# RoBeast_Driver.net
KiCad netlist of a schematic drawn in Altium Designer
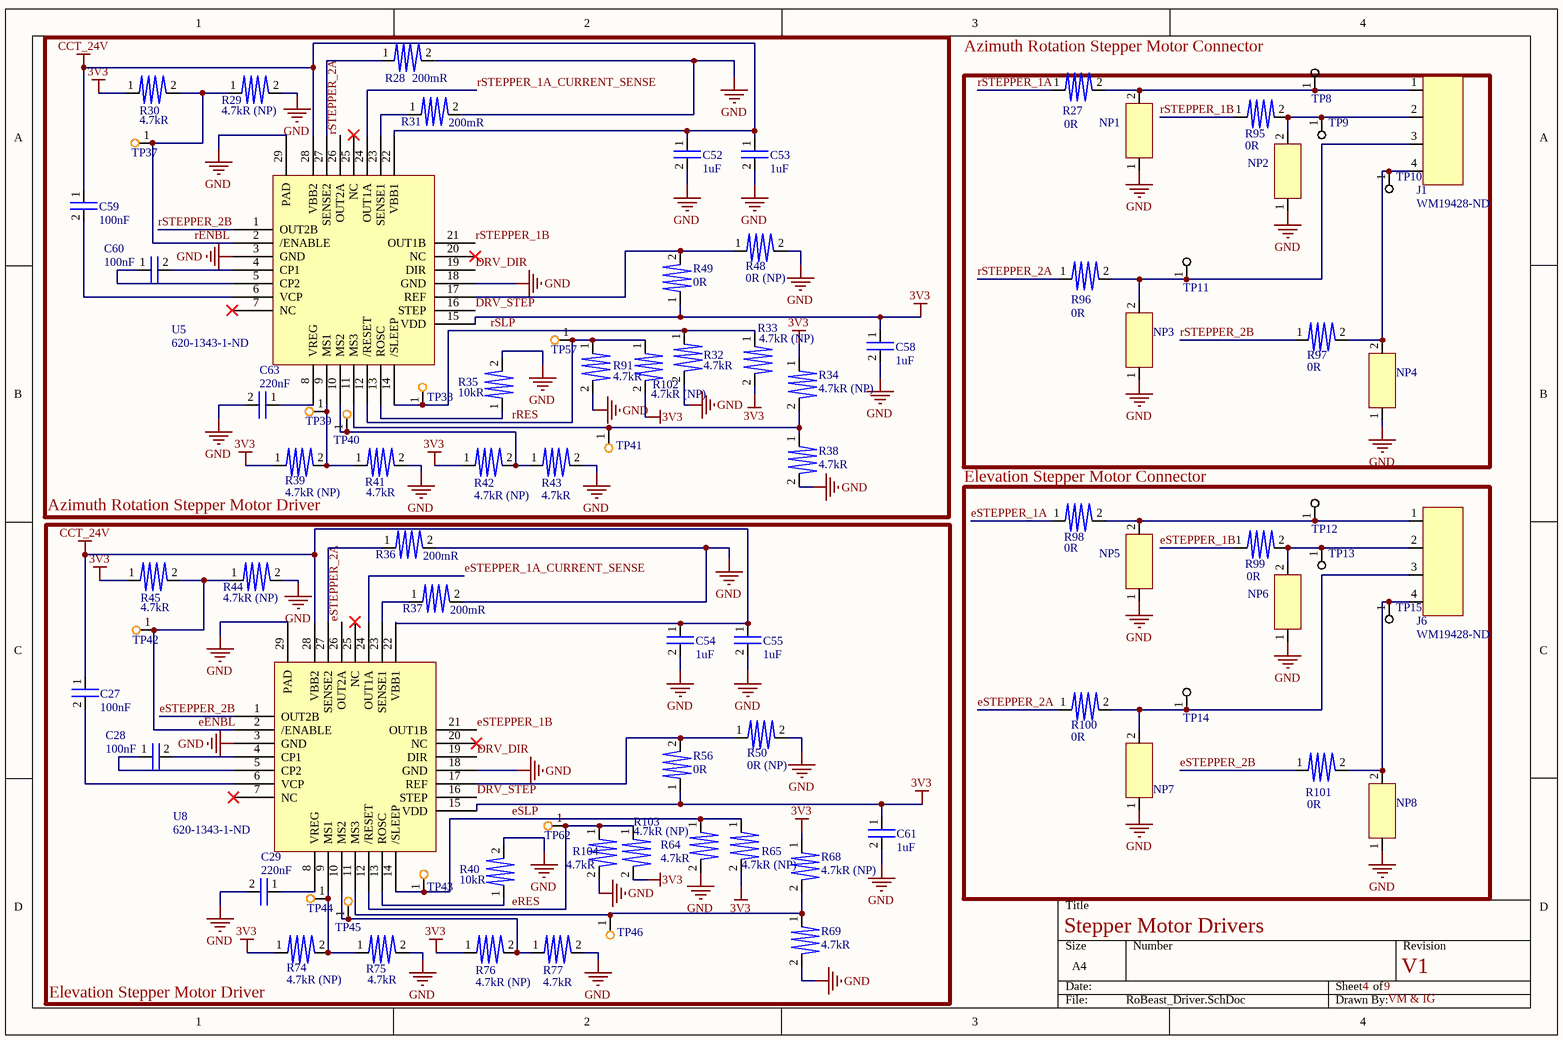
[diagram p0: RoBeast_Driver.SchDoc]

(export (version "E")
  (design (tool "Eeschema 10.0.6"))
  (components
    (comp (ref "C27")
      (value "100nF")
      (footprint "0805")
      (fields
        (field (name "MANUFACTURER") "KEMET")
        (field (name "MANUFACTURER PART NUMBER") "C0805C104J5RACTU")
      )
      (libsource (lib "RoBeast_Schematic_Library") (part "C0805C104J5RAC7800"))
    )
    (comp (ref "C28")
      (value "100nF")
      (footprint "0805")
      (fields
        (field (name "MANUFACTURER") "KEMET")
        (field (name "MANUFACTURER PART NUMBER") "C0805C104J5RACTU")
      )
      (libsource (lib "RoBeast_Schematic_Library") (part "C0805C104J5RAC7800"))
    )
    (comp (ref "C29")
      (value "220nF")
      (footprint "0805")
      (fields
        (field (name "MANUFACTURER") "KEMET")
        (field (name "MANUFACTURER PART NUMBER") "C0805C224J1RECAUTO")
      )
      (libsource (lib "RoBeast_Schematic_Library") (part "C0805C224J1RECAUTO"))
    )
    (comp (ref "C52")
      (value "1uF")
      (footprint "0805")
      (fields
        (field (name "MANUFACTURER") "Yageo")
        (field (name "MANUFACTURER PART NUMBER") "CC0805JKX7R9BB105")
      )
      (libsource (lib "RoBeast_Schematic_Library") (part "CC0805JKX7R9BB105"))
    )
    (comp (ref "C53")
      (value "1uF")
      (footprint "0805")
      (fields
        (field (name "MANUFACTURER") "Yageo")
        (field (name "MANUFACTURER PART NUMBER") "CC0805JKX7R9BB105")
      )
      (libsource (lib "RoBeast_Schematic_Library") (part "CC0805JKX7R9BB105"))
    )
    (comp (ref "C54")
      (value "1uF")
      (footprint "0805")
      (fields
        (field (name "MANUFACTURER") "Yageo")
        (field (name "MANUFACTURER PART NUMBER") "CC0805JKX7R9BB105")
      )
      (libsource (lib "RoBeast_Schematic_Library") (part "CC0805JKX7R9BB105"))
    )
    (comp (ref "C55")
      (value "1uF")
      (footprint "0805")
      (fields
        (field (name "MANUFACTURER") "Yageo")
        (field (name "MANUFACTURER PART NUMBER") "CC0805JKX7R9BB105")
      )
      (libsource (lib "RoBeast_Schematic_Library") (part "CC0805JKX7R9BB105"))
    )
    (comp (ref "C58")
      (value "1uF")
      (footprint "0805")
      (fields
        (field (name "MANUFACTURER") "Yageo")
        (field (name "MANUFACTURER PART NUMBER") "CC0805JKX7R9BB105")
      )
      (libsource (lib "RoBeast_Schematic_Library") (part "CC0805JKX7R9BB105"))
    )
    (comp (ref "C59")
      (value "100nF")
      (footprint "0805")
      (fields
        (field (name "MANUFACTURER") "KEMET")
        (field (name "MANUFACTURER PART NUMBER") "C0805C104J5RACTU")
      )
      (libsource (lib "RoBeast_Schematic_Library") (part "C0805C104J5RAC7800"))
    )
    (comp (ref "C60")
      (value "100nF")
      (footprint "0805")
      (fields
        (field (name "MANUFACTURER") "KEMET")
        (field (name "MANUFACTURER PART NUMBER") "C0805C104J5RACTU")
      )
      (libsource (lib "RoBeast_Schematic_Library") (part "C0805C104J5RAC7800"))
    )
    (comp (ref "C61")
      (value "1uF")
      (footprint "0805")
      (fields
        (field (name "MANUFACTURER") "Yageo")
        (field (name "MANUFACTURER PART NUMBER") "CC0805JKX7R9BB105")
      )
      (libsource (lib "RoBeast_Schematic_Library") (part "CC0805JKX7R9BB105"))
    )
    (comp (ref "C63")
      (value "220nF")
      (footprint "0805")
      (fields
        (field (name "MANUFACTURER") "KEMET")
        (field (name "MANUFACTURER PART NUMBER") "C0805C224J1RECAUTO")
      )
      (libsource (lib "RoBeast_Schematic_Library") (part "C0805C224J1RECAUTO"))
    )
    (comp (ref "J1")
      (value "4 Pin Connector")
      (footprint "0015246043")
      (description "Rectangular Power Connector, 4 Contact(s), Male, Solder Terminal, Receptacle")
      (fields
        (field (name "MANUFACTURER") "Molex")
        (field (name "MANUFACTURER PART NUMBER") "15-24-6043")
        (field (name "SUPPLIER PART NUMBER") "WM19428-ND")
      )
      (libsource (lib "RoBeast_Schematic_Library") (part "0015246043"))
    )
    (comp (ref "J6")
      (value "4 Pin Connector")
      (footprint "0015246043")
      (description "Rectangular Power Connector, 4 Contact(s), Male, Solder Terminal, Receptacle")
      (fields
        (field (name "MANUFACTURER") "Molex")
        (field (name "MANUFACTURER PART NUMBER") "15-24-6043")
        (field (name "SUPPLIER PART NUMBER") "WM19428-ND")
      )
      (libsource (lib "RoBeast_Schematic_Library") (part "0015246043"))
    )
    (comp (ref "NP1")
      (value "Not Populated")
      (footprint "0805")
      (libsource (lib "RoBeast_Schematic_Library") (part "NP"))
    )
    (comp (ref "NP2")
      (value "Not Populated")
      (footprint "0805")
      (libsource (lib "RoBeast_Schematic_Library") (part "NP"))
    )
    (comp (ref "NP3")
      (value "Not Populated")
      (footprint "0805")
      (libsource (lib "RoBeast_Schematic_Library") (part "NP"))
    )
    (comp (ref "NP4")
      (value "Not Populated")
      (footprint "0805")
      (libsource (lib "RoBeast_Schematic_Library") (part "NP"))
    )
    (comp (ref "NP5")
      (value "Not Populated")
      (footprint "0805")
      (libsource (lib "RoBeast_Schematic_Library") (part "NP"))
    )
    (comp (ref "NP6")
      (value "Not Populated")
      (footprint "0805")
      (libsource (lib "RoBeast_Schematic_Library") (part "NP"))
    )
    (comp (ref "NP7")
      (value "Not Populated")
      (footprint "0805")
      (libsource (lib "RoBeast_Schematic_Library") (part "NP"))
    )
    (comp (ref "NP8")
      (value "Not Populated")
      (footprint "0805")
      (libsource (lib "RoBeast_Schematic_Library") (part "NP"))
    )
    (comp (ref "R27")
      (value "0R")
      (footprint "0805")
      (description "Fixed Resistor, Metal Glaze/thick Film, 0.125W, 0ohm, Surface Mount, 0805")
      (fields
        (field (name "MANUFACTURER") "Stackpole Electronics")
        (field (name "MANUFACTURER PART NUMBER") "RMCF0805ZT0R00")
      )
      (libsource (lib "RoBeast_Schematic_Library") (part "RMCF0805ZT0R00"))
    )
    (comp (ref "R28")
      (value "200mR")
      (footprint "0805")
      (description "Res 0805 50PPM 0.2 Ohm 1.0% 0.75")
      (fields
        (field (name "MANUFACTURER") "Thin Film Tech")
        (field (name "MANUFACTURER PART NUMBER") "D1WEL0805CR200F-T5")
      )
      (libsource (lib "RoBeast_Schematic_Library") (part "D1WEL0805CR200F-T5"))
    )
    (comp (ref "R29")
      (value "4.7kR (NP)")
      (footprint "0805")
      (fields
        (field (name "MANUFACTURER") "Vishay Dale")
        (field (name "MANUFACTURER PART NUMBER") "RCC08054K70FKEA")
      )
      (libsource (lib "RoBeast_Schematic_Library") (part "RCC08054K70FKEA"))
    )
    (comp (ref "R30")
      (value "4.7kR")
      (footprint "0805")
      (fields
        (field (name "MANUFACTURER") "Vishay Dale")
        (field (name "MANUFACTURER PART NUMBER") "RCC08054K70FKEA")
      )
      (libsource (lib "RoBeast_Schematic_Library") (part "RCC08054K70FKEA"))
    )
    (comp (ref "R31")
      (value "200mR")
      (footprint "0805")
      (description "Res 0805 50PPM 0.2 Ohm 1.0% 0.75")
      (fields
        (field (name "MANUFACTURER") "Thin Film Tech")
        (field (name "MANUFACTURER PART NUMBER") "D1WEL0805CR200F-T5")
      )
      (libsource (lib "RoBeast_Schematic_Library") (part "D1WEL0805CR200F-T5"))
    )
    (comp (ref "R32")
      (value "4.7kR")
      (footprint "0805")
      (fields
        (field (name "MANUFACTURER") "Vishay Dale")
        (field (name "MANUFACTURER PART NUMBER") "RCC08054K70FKEA")
      )
      (libsource (lib "RoBeast_Schematic_Library") (part "RCC08054K70FKEA"))
    )
    (comp (ref "R33")
      (value "4.7kR (NP)")
      (footprint "0805")
      (fields
        (field (name "MANUFACTURER") "Vishay Dale")
        (field (name "MANUFACTURER PART NUMBER") "RCC08054K70FKEA")
      )
      (libsource (lib "RoBeast_Schematic_Library") (part "RCC08054K70FKEA"))
    )
    (comp (ref "R34")
      (value "4.7kR (NP)")
      (footprint "0805")
      (fields
        (field (name "MANUFACTURER") "Vishay Dale")
        (field (name "MANUFACTURER PART NUMBER") "RCC08054K70FKEA")
      )
      (libsource (lib "RoBeast_Schematic_Library") (part "RCC08054K70FKEA"))
    )
    (comp (ref "R35")
      (value "10kR")
      (footprint "0805")
      (fields
        (field (name "MANUFACTURER") "Stackpole Electronics")
        (field (name "MANUFACTURER PART NUMBER") "RMCF0805FT10K0")
        (field (name "TOLERANCE") "1%")
      )
      (libsource (lib "RoBeast_Schematic_Library") (part "RMCF0805FT10K0"))
    )
    (comp (ref "R36")
      (value "200mR")
      (footprint "0805")
      (description "Res 0805 50PPM 0.2 Ohm 1.0% 0.75")
      (fields
        (field (name "MANUFACTURER") "Thin Film Tech")
        (field (name "MANUFACTURER PART NUMBER") "D1WEL0805CR200F-T5")
      )
      (libsource (lib "RoBeast_Schematic_Library") (part "D1WEL0805CR200F-T5"))
    )
    (comp (ref "R37")
      (value "200mR")
      (footprint "0805")
      (description "Res 0805 50PPM 0.2 Ohm 1.0% 0.75")
      (fields
        (field (name "MANUFACTURER") "Thin Film Tech")
        (field (name "MANUFACTURER PART NUMBER") "D1WEL0805CR200F-T5")
      )
      (libsource (lib "RoBeast_Schematic_Library") (part "D1WEL0805CR200F-T5"))
    )
    (comp (ref "R38")
      (value "4.7kR")
      (footprint "0805")
      (fields
        (field (name "MANUFACTURER") "Vishay Dale")
        (field (name "MANUFACTURER PART NUMBER") "RCC08054K70FKEA")
      )
      (libsource (lib "RoBeast_Schematic_Library") (part "RCC08054K70FKEA"))
    )
    (comp (ref "R39")
      (value "4.7kR (NP)")
      (footprint "0805")
      (fields
        (field (name "MANUFACTURER") "Vishay Dale")
        (field (name "MANUFACTURER PART NUMBER") "RCC08054K70FKEA")
      )
      (libsource (lib "RoBeast_Schematic_Library") (part "RCC08054K70FKEA"))
    )
    (comp (ref "R40")
      (value "10kR")
      (footprint "0805")
      (fields
        (field (name "MANUFACTURER") "Stackpole Electronics")
        (field (name "MANUFACTURER PART NUMBER") "RMCF0805FT10K0")
        (field (name "TOLERANCE") "1%")
      )
      (libsource (lib "RoBeast_Schematic_Library") (part "RMCF0805FT10K0"))
    )
    (comp (ref "R41")
      (value "4.7kR")
      (footprint "0805")
      (fields
        (field (name "MANUFACTURER") "Vishay Dale")
        (field (name "MANUFACTURER PART NUMBER") "RCC08054K70FKEA")
      )
      (libsource (lib "RoBeast_Schematic_Library") (part "RCC08054K70FKEA"))
    )
    (comp (ref "R42")
      (value "4.7kR (NP)")
      (footprint "0805")
      (fields
        (field (name "MANUFACTURER") "Vishay Dale")
        (field (name "MANUFACTURER PART NUMBER") "RCC08054K70FKEA")
      )
      (libsource (lib "RoBeast_Schematic_Library") (part "RCC08054K70FKEA"))
    )
    (comp (ref "R43")
      (value "4.7kR")
      (footprint "0805")
      (fields
        (field (name "MANUFACTURER") "Vishay Dale")
        (field (name "MANUFACTURER PART NUMBER") "RCC08054K70FKEA")
      )
      (libsource (lib "RoBeast_Schematic_Library") (part "RCC08054K70FKEA"))
    )
    (comp (ref "R44")
      (value "4.7kR (NP)")
      (footprint "0805")
      (fields
        (field (name "MANUFACTURER") "Vishay Dale")
        (field (name "MANUFACTURER PART NUMBER") "RCC08054K70FKEA")
      )
      (libsource (lib "RoBeast_Schematic_Library") (part "RCC08054K70FKEA"))
    )
    (comp (ref "R45")
      (value "4.7kR")
      (footprint "0805")
      (fields
        (field (name "MANUFACTURER") "Vishay Dale")
        (field (name "MANUFACTURER PART NUMBER") "RCC08054K70FKEA")
      )
      (libsource (lib "RoBeast_Schematic_Library") (part "RCC08054K70FKEA"))
    )
    (comp (ref "R48")
      (value "0R (NP)")
      (footprint "0805")
      (description "Fixed Resistor, Metal Glaze/thick Film, 0.125W, 0ohm, Surface Mount, 0805")
      (fields
        (field (name "MANUFACTURER") "Stackpole Electronics")
        (field (name "MANUFACTURER PART NUMBER") "RMCF0805ZT0R00")
      )
      (libsource (lib "RoBeast_Schematic_Library") (part "RMCF0805ZT0R00"))
    )
    (comp (ref "R49")
      (value "0R")
      (footprint "0805")
      (description "Fixed Resistor, Metal Glaze/thick Film, 0.125W, 0ohm, Surface Mount, 0805")
      (fields
        (field (name "MANUFACTURER") "Stackpole Electronics")
        (field (name "MANUFACTURER PART NUMBER") "RMCF0805ZT0R00")
      )
      (libsource (lib "RoBeast_Schematic_Library") (part "RMCF0805ZT0R00"))
    )
    (comp (ref "R50")
      (value "0R (NP)")
      (footprint "0805")
      (description "Fixed Resistor, Metal Glaze/thick Film, 0.125W, 0ohm, Surface Mount, 0805")
      (fields
        (field (name "MANUFACTURER") "Stackpole Electronics")
        (field (name "MANUFACTURER PART NUMBER") "RMCF0805ZT0R00")
      )
      (libsource (lib "RoBeast_Schematic_Library") (part "RMCF0805ZT0R00"))
    )
    (comp (ref "R56")
      (value "0R")
      (footprint "0805")
      (description "Fixed Resistor, Metal Glaze/thick Film, 0.125W, 0ohm, Surface Mount, 0805")
      (fields
        (field (name "MANUFACTURER") "Stackpole Electronics")
        (field (name "MANUFACTURER PART NUMBER") "RMCF0805ZT0R00")
      )
      (libsource (lib "RoBeast_Schematic_Library") (part "RMCF0805ZT0R00"))
    )
    (comp (ref "R64")
      (value "4.7kR")
      (footprint "0805")
      (fields
        (field (name "MANUFACTURER") "Vishay Dale")
        (field (name "MANUFACTURER PART NUMBER") "RCC08054K70FKEA")
      )
      (libsource (lib "RoBeast_Schematic_Library") (part "RCC08054K70FKEA"))
    )
    (comp (ref "R65")
      (value "4.7kR (NP)")
      (footprint "0805")
      (fields
        (field (name "MANUFACTURER") "Vishay Dale")
        (field (name "MANUFACTURER PART NUMBER") "RCC08054K70FKEA")
      )
      (libsource (lib "RoBeast_Schematic_Library") (part "RCC08054K70FKEA"))
    )
    (comp (ref "R68")
      (value "4.7kR (NP)")
      (footprint "0805")
      (fields
        (field (name "MANUFACTURER") "Vishay Dale")
        (field (name "MANUFACTURER PART NUMBER") "RCC08054K70FKEA")
      )
      (libsource (lib "RoBeast_Schematic_Library") (part "RCC08054K70FKEA"))
    )
    (comp (ref "R69")
      (value "4.7kR")
      (footprint "0805")
      (fields
        (field (name "MANUFACTURER") "Vishay Dale")
        (field (name "MANUFACTURER PART NUMBER") "RCC08054K70FKEA")
      )
      (libsource (lib "RoBeast_Schematic_Library") (part "RCC08054K70FKEA"))
    )
    (comp (ref "R74")
      (value "4.7kR (NP)")
      (footprint "0805")
      (fields
        (field (name "MANUFACTURER") "Vishay Dale")
        (field (name "MANUFACTURER PART NUMBER") "RCC08054K70FKEA")
      )
      (libsource (lib "RoBeast_Schematic_Library") (part "RCC08054K70FKEA"))
    )
    (comp (ref "R75")
      (value "4.7kR")
      (footprint "0805")
      (fields
        (field (name "MANUFACTURER") "Vishay Dale")
        (field (name "MANUFACTURER PART NUMBER") "RCC08054K70FKEA")
      )
      (libsource (lib "RoBeast_Schematic_Library") (part "RCC08054K70FKEA"))
    )
    (comp (ref "R76")
      (value "4.7kR (NP)")
      (footprint "0805")
      (fields
        (field (name "MANUFACTURER") "Vishay Dale")
        (field (name "MANUFACTURER PART NUMBER") "RCC08054K70FKEA")
      )
      (libsource (lib "RoBeast_Schematic_Library") (part "RCC08054K70FKEA"))
    )
    (comp (ref "R77")
      (value "4.7kR")
      (footprint "0805")
      (fields
        (field (name "MANUFACTURER") "Vishay Dale")
        (field (name "MANUFACTURER PART NUMBER") "RCC08054K70FKEA")
      )
      (libsource (lib "RoBeast_Schematic_Library") (part "RCC08054K70FKEA"))
    )
    (comp (ref "R91")
      (value "4.7kR")
      (footprint "0805")
      (fields
        (field (name "MANUFACTURER") "Vishay Dale")
        (field (name "MANUFACTURER PART NUMBER") "RCC08054K70FKEA")
      )
      (libsource (lib "RoBeast_Schematic_Library") (part "RCC08054K70FKEA"))
    )
    (comp (ref "R95")
      (value "0R")
      (footprint "0805")
      (description "Fixed Resistor, Metal Glaze/thick Film, 0.125W, 0ohm, Surface Mount, 0805")
      (fields
        (field (name "MANUFACTURER") "Stackpole Electronics")
        (field (name "MANUFACTURER PART NUMBER") "RMCF0805ZT0R00")
      )
      (libsource (lib "RoBeast_Schematic_Library") (part "RMCF0805ZT0R00"))
    )
    (comp (ref "R96")
      (value "0R")
      (footprint "0805")
      (description "Fixed Resistor, Metal Glaze/thick Film, 0.125W, 0ohm, Surface Mount, 0805")
      (fields
        (field (name "MANUFACTURER") "Stackpole Electronics")
        (field (name "MANUFACTURER PART NUMBER") "RMCF0805ZT0R00")
      )
      (libsource (lib "RoBeast_Schematic_Library") (part "RMCF0805ZT0R00"))
    )
    (comp (ref "R97")
      (value "0R")
      (footprint "0805")
      (description "Fixed Resistor, Metal Glaze/thick Film, 0.125W, 0ohm, Surface Mount, 0805")
      (fields
        (field (name "MANUFACTURER") "Stackpole Electronics")
        (field (name "MANUFACTURER PART NUMBER") "RMCF0805ZT0R00")
      )
      (libsource (lib "RoBeast_Schematic_Library") (part "RMCF0805ZT0R00"))
    )
    (comp (ref "R98")
      (value "0R")
      (footprint "0805")
      (description "Fixed Resistor, Metal Glaze/thick Film, 0.125W, 0ohm, Surface Mount, 0805")
      (fields
        (field (name "MANUFACTURER") "Stackpole Electronics")
        (field (name "MANUFACTURER PART NUMBER") "RMCF0805ZT0R00")
      )
      (libsource (lib "RoBeast_Schematic_Library") (part "RMCF0805ZT0R00"))
    )
    (comp (ref "R99")
      (value "0R")
      (footprint "0805")
      (description "Fixed Resistor, Metal Glaze/thick Film, 0.125W, 0ohm, Surface Mount, 0805")
      (fields
        (field (name "MANUFACTURER") "Stackpole Electronics")
        (field (name "MANUFACTURER PART NUMBER") "RMCF0805ZT0R00")
      )
      (libsource (lib "RoBeast_Schematic_Library") (part "RMCF0805ZT0R00"))
    )
    (comp (ref "R100")
      (value "0R")
      (footprint "0805")
      (description "Fixed Resistor, Metal Glaze/thick Film, 0.125W, 0ohm, Surface Mount, 0805")
      (fields
        (field (name "MANUFACTURER") "Stackpole Electronics")
        (field (name "MANUFACTURER PART NUMBER") "RMCF0805ZT0R00")
      )
      (libsource (lib "RoBeast_Schematic_Library") (part "RMCF0805ZT0R00"))
    )
    (comp (ref "R101")
      (value "0R")
      (footprint "0805")
      (description "Fixed Resistor, Metal Glaze/thick Film, 0.125W, 0ohm, Surface Mount, 0805")
      (fields
        (field (name "MANUFACTURER") "Stackpole Electronics")
        (field (name "MANUFACTURER PART NUMBER") "RMCF0805ZT0R00")
      )
      (libsource (lib "RoBeast_Schematic_Library") (part "RMCF0805ZT0R00"))
    )
    (comp (ref "R102")
      (value "4.7kR (NP)")
      (footprint "0805")
      (fields
        (field (name "MANUFACTURER") "Vishay Dale")
        (field (name "MANUFACTURER PART NUMBER") "RCC08054K70FKEA")
      )
      (libsource (lib "RoBeast_Schematic_Library") (part "RCC08054K70FKEA"))
    )
    (comp (ref "R103")
      (value "4.7kR (NP)")
      (footprint "0805")
      (fields
        (field (name "MANUFACTURER") "Vishay Dale")
        (field (name "MANUFACTURER PART NUMBER") "RCC08054K70FKEA")
      )
      (libsource (lib "RoBeast_Schematic_Library") (part "RCC08054K70FKEA"))
    )
    (comp (ref "R104")
      (value "4.7kR")
      (footprint "0805")
      (fields
        (field (name "MANUFACTURER") "Vishay Dale")
        (field (name "MANUFACTURER PART NUMBER") "RCC08054K70FKEA")
      )
      (libsource (lib "RoBeast_Schematic_Library") (part "RCC08054K70FKEA"))
    )
    (comp (ref "TP8")
      (value "Test Point")
      (footprint "RCWCTE")
      (description "Testing/Accessories")
      (fields (field (name "MANUFACTURER") "KOA Speer") (field (name "MANUFACTURER PART NUMBER") "RCWCTE"))
      (libsource (lib "RoBeast_Schematic_Library") (part "RCWCTE"))
    )
    (comp (ref "TP9")
      (value "Test Point")
      (footprint "RCWCTE")
      (description "Testing/Accessories")
      (fields (field (name "MANUFACTURER") "KOA Speer") (field (name "MANUFACTURER PART NUMBER") "RCWCTE"))
      (libsource (lib "RoBeast_Schematic_Library") (part "RCWCTE"))
    )
    (comp (ref "TP10")
      (value "Test Point")
      (footprint "RCWCTE")
      (description "Testing/Accessories")
      (fields (field (name "MANUFACTURER") "KOA Speer") (field (name "MANUFACTURER PART NUMBER") "RCWCTE"))
      (libsource (lib "RoBeast_Schematic_Library") (part "RCWCTE"))
    )
    (comp (ref "TP11")
      (value "Test Point")
      (footprint "RCWCTE")
      (description "Testing/Accessories")
      (fields (field (name "MANUFACTURER") "KOA Speer") (field (name "MANUFACTURER PART NUMBER") "RCWCTE"))
      (libsource (lib "RoBeast_Schematic_Library") (part "RCWCTE"))
    )
    (comp (ref "TP12")
      (value "Test Point")
      (footprint "RCWCTE")
      (description "Testing/Accessories")
      (fields (field (name "MANUFACTURER") "KOA Speer") (field (name "MANUFACTURER PART NUMBER") "RCWCTE"))
      (libsource (lib "RoBeast_Schematic_Library") (part "RCWCTE"))
    )
    (comp (ref "TP13")
      (value "Test Point")
      (footprint "RCWCTE")
      (description "Testing/Accessories")
      (fields (field (name "MANUFACTURER") "KOA Speer") (field (name "MANUFACTURER PART NUMBER") "RCWCTE"))
      (libsource (lib "RoBeast_Schematic_Library") (part "RCWCTE"))
    )
    (comp (ref "TP14")
      (value "Test Point")
      (footprint "RCWCTE")
      (description "Testing/Accessories")
      (fields (field (name "MANUFACTURER") "KOA Speer") (field (name "MANUFACTURER PART NUMBER") "RCWCTE"))
      (libsource (lib "RoBeast_Schematic_Library") (part "RCWCTE"))
    )
    (comp (ref "TP15")
      (value "Test Point")
      (footprint "RCWCTE")
      (description "Testing/Accessories")
      (fields (field (name "MANUFACTURER") "KOA Speer") (field (name "MANUFACTURER PART NUMBER") "RCWCTE"))
      (libsource (lib "RoBeast_Schematic_Library") (part "RCWCTE"))
    )
    (comp (ref "TP37")
      (value "Test Point")
      (footprint "Test Point")
      (libsource (lib "RoBeast_Schematic_Library") (part "Test Point"))
    )
    (comp (ref "TP38")
      (value "Test Point")
      (footprint "Test Point")
      (libsource (lib "RoBeast_Schematic_Library") (part "Test Point"))
    )
    (comp (ref "TP39")
      (value "Test Point")
      (footprint "Test Point")
      (libsource (lib "RoBeast_Schematic_Library") (part "Test Point"))
    )
    (comp (ref "TP40")
      (value "Test Point")
      (footprint "Test Point")
      (libsource (lib "RoBeast_Schematic_Library") (part "Test Point"))
    )
    (comp (ref "TP41")
      (value "Test Point")
      (footprint "Test Point")
      (libsource (lib "RoBeast_Schematic_Library") (part "Test Point"))
    )
    (comp (ref "TP42")
      (value "Test Point")
      (footprint "Test Point")
      (libsource (lib "RoBeast_Schematic_Library") (part "Test Point"))
    )
    (comp (ref "TP43")
      (value "Test Point")
      (footprint "Test Point")
      (libsource (lib "RoBeast_Schematic_Library") (part "Test Point"))
    )
    (comp (ref "TP44")
      (value "Test Point")
      (footprint "Test Point")
      (libsource (lib "RoBeast_Schematic_Library") (part "Test Point"))
    )
    (comp (ref "TP45")
      (value "Test Point")
      (footprint "Test Point")
      (libsource (lib "RoBeast_Schematic_Library") (part "Test Point"))
    )
    (comp (ref "TP46")
      (value "Test Point")
      (footprint "Test Point")
      (libsource (lib "RoBeast_Schematic_Library") (part "Test Point"))
    )
    (comp (ref "TP57")
      (value "Test Point")
      (footprint "Test Point")
      (libsource (lib "RoBeast_Schematic_Library") (part "Test Point"))
    )
    (comp (ref "TP62")
      (value "Test Point")
      (footprint "Test Point")
      (libsource (lib "RoBeast_Schematic_Library") (part "Test Point"))
    )
    (comp (ref "U5")
      (value "Stepper Motor Driver")
      (footprint "A4988SETTR-T")
      (description "Stepper Motor Controller, 2A, DMOS")
      (fields
        (field (name "MANUFACTURER") "Allegro MicroSystems")
        (field (name "MANUFACTURER PART NUMBER") "A4988SETTR-T")
        (field (name "SUPPLIER PART NUMBER") "620-1343-1-ND")
      )
      (libsource (lib "RoBeast_Schematic_Library") (part "A4988SETTR-T"))
    )
    (comp (ref "U8")
      (value "Stepper Motor Driver")
      (footprint "A4988SETTR-T")
      (description "Stepper Motor Controller, 2A, DMOS")
      (fields
        (field (name "MANUFACTURER") "Allegro MicroSystems")
        (field (name "MANUFACTURER PART NUMBER") "A4988SETTR-T")
        (field (name "SUPPLIER PART NUMBER") "620-1343-1-ND")
      )
      (libsource (lib "RoBeast_Schematic_Library") (part "A4988SETTR-T"))
    )
  )
  (nets
    (net (code "1") (name "/DRV_DIR") (class "Default")
      (node (ref "U5") (pin "19") (pinfunction "DIR_19") (pintype "passive"))
      (node (ref "U8") (pin "19") (pinfunction "DIR_19") (pintype "passive"))
    )
    (net (code "2") (name "/DRV_STEP") (class "Default")
      (node (ref "U5") (pin "16") (pinfunction "STEP_16") (pintype "passive"))
      (node (ref "U8") (pin "16") (pinfunction "STEP_16") (pintype "passive"))
    )
    (net (code "3") (name "/eENBL") (class "Default")
      (node (ref "R44") (pin "1") (pinfunction "1_1") (pintype "passive"))
      (node (ref "R45") (pin "2") (pinfunction "2_2") (pintype "passive"))
      (node (ref "TP42") (pin "1") (pinfunction "1_1") (pintype "passive"))
      (node (ref "U8") (pin "2") (pinfunction "/ENABLE_2") (pintype "passive"))
    )
    (net (code "4") (name "/eRES") (class "Default")
      (node (ref "R103") (pin "1") (pinfunction "1_1") (pintype "passive"))
      (node (ref "R104") (pin "1") (pinfunction "1_1") (pintype "passive"))
      (node (ref "TP62") (pin "1") (pinfunction "1_1") (pintype "passive"))
      (node (ref "U8") (pin "12") (pinfunction "/RESET_12") (pintype "passive"))
    )
    (net (code "5") (name "/eSLP") (class "Default")
      (node (ref "R64") (pin "1") (pinfunction "1_1") (pintype "passive"))
      (node (ref "R65") (pin "1") (pinfunction "1_1") (pintype "passive"))
      (node (ref "TP43") (pin "1") (pinfunction "1_1") (pintype "passive"))
      (node (ref "U8") (pin "14") (pinfunction "/SLEEP_14") (pintype "passive"))
    )
    (net (code "6") (name "/eSTEPPER_1A") (class "Default")
      (node (ref "R98") (pin "1") (pinfunction "1_1") (pintype "passive"))
    )
    (net (code "7") (name "/eSTEPPER_1A_CURRENT_SENSE") (class "Default")
      (node (ref "U8") (pin "24") (pinfunction "OUT1A_24") (pintype "passive"))
    )
    (net (code "8") (name "/eSTEPPER_1B") (class "Default")
      (node (ref "R99") (pin "1") (pinfunction "1_1") (pintype "passive"))
      (node (ref "U8") (pin "21") (pinfunction "OUT1B_21") (pintype "passive"))
    )
    (net (code "9") (name "/eSTEPPER_2A") (class "Default")
      (node (ref "R100") (pin "1") (pinfunction "1_1") (pintype "passive"))
      (node (ref "U8") (pin "26") (pinfunction "OUT2A_26") (pintype "passive"))
    )
    (net (code "10") (name "/eSTEPPER_2B") (class "Default")
      (node (ref "R101") (pin "1") (pinfunction "1_1") (pintype "passive"))
      (node (ref "U8") (pin "1") (pinfunction "OUT2B_1") (pintype "passive"))
    )
    (net (code "11") (name "/rENBL") (class "Default")
      (node (ref "R29") (pin "1") (pinfunction "1_1") (pintype "passive"))
      (node (ref "R30") (pin "2") (pinfunction "2_2") (pintype "passive"))
      (node (ref "TP37") (pin "1") (pinfunction "1_1") (pintype "passive"))
      (node (ref "U5") (pin "2") (pinfunction "/ENABLE_2") (pintype "passive"))
    )
    (net (code "12") (name "/rRES") (class "Default")
      (node (ref "R102") (pin "1") (pinfunction "1_1") (pintype "passive"))
      (node (ref "R91") (pin "1") (pinfunction "1_1") (pintype "passive"))
      (node (ref "TP57") (pin "1") (pinfunction "1_1") (pintype "passive"))
      (node (ref "U5") (pin "12") (pinfunction "/RESET_12") (pintype "passive"))
    )
    (net (code "13") (name "/rSLP") (class "Default")
      (node (ref "R32") (pin "1") (pinfunction "1_1") (pintype "passive"))
      (node (ref "R33") (pin "1") (pinfunction "1_1") (pintype "passive"))
      (node (ref "TP38") (pin "1") (pinfunction "1_1") (pintype "passive"))
      (node (ref "U5") (pin "14") (pinfunction "/SLEEP_14") (pintype "passive"))
    )
    (net (code "14") (name "/rSTEPPER_1A") (class "Default")
      (node (ref "R27") (pin "1") (pinfunction "1_1") (pintype "passive"))
    )
    (net (code "15") (name "/rSTEPPER_1A_CURRENT_SENSE") (class "Default")
      (node (ref "U5") (pin "24") (pinfunction "OUT1A_24") (pintype "passive"))
    )
    (net (code "16") (name "/rSTEPPER_1B") (class "Default")
      (node (ref "R95") (pin "1") (pinfunction "1_1") (pintype "passive"))
      (node (ref "U5") (pin "21") (pinfunction "OUT1B_21") (pintype "passive"))
    )
    (net (code "17") (name "/rSTEPPER_2A") (class "Default")
      (node (ref "R96") (pin "1") (pinfunction "1_1") (pintype "passive"))
      (node (ref "U5") (pin "26") (pinfunction "OUT2A_26") (pintype "passive"))
    )
    (net (code "18") (name "/rSTEPPER_2B") (class "Default")
      (node (ref "R97") (pin "1") (pinfunction "1_1") (pintype "passive"))
      (node (ref "U5") (pin "1") (pinfunction "OUT2B_1") (pintype "passive"))
    )
    (net (code "19") (name "3V3") (class "Default")
      (node (ref "C58") (pin "1") (pinfunction "1_1") (pintype "passive"))
      (node (ref "C61") (pin "1") (pinfunction "1_1") (pintype "passive"))
      (node (ref "R102") (pin "2") (pinfunction "2_2") (pintype "passive"))
      (node (ref "R103") (pin "2") (pinfunction "2_2") (pintype "passive"))
      (node (ref "R30") (pin "1") (pinfunction "1_1") (pintype "passive"))
      (node (ref "R33") (pin "2") (pinfunction "2_2") (pintype "passive"))
      (node (ref "R34") (pin "1") (pinfunction "1_1") (pintype "passive"))
      (node (ref "R39") (pin "1") (pinfunction "1_1") (pintype "passive"))
      (node (ref "R42") (pin "1") (pinfunction "1_1") (pintype "passive"))
      (node (ref "R45") (pin "1") (pinfunction "1_1") (pintype "passive"))
      (node (ref "R49") (pin "1") (pinfunction "1_1") (pintype "passive"))
      (node (ref "R56") (pin "1") (pinfunction "1_1") (pintype "passive"))
      (node (ref "R65") (pin "2") (pinfunction "2_2") (pintype "passive"))
      (node (ref "R68") (pin "1") (pinfunction "1_1") (pintype "passive"))
      (node (ref "R74") (pin "1") (pinfunction "1_1") (pintype "passive"))
      (node (ref "R76") (pin "1") (pinfunction "1_1") (pintype "passive"))
      (node (ref "U5") (pin "15") (pinfunction "VDD_15") (pintype "passive"))
      (node (ref "U8") (pin "15") (pinfunction "VDD_15") (pintype "passive"))
    )
    (net (code "20") (name "CCT_24V") (class "Default")
      (node (ref "C27") (pin "1") (pinfunction "1_1") (pintype "passive"))
      (node (ref "C52") (pin "1") (pinfunction "1_1") (pintype "passive"))
      (node (ref "C53") (pin "1") (pinfunction "1_1") (pintype "passive"))
      (node (ref "C54") (pin "1") (pinfunction "1_1") (pintype "passive"))
      (node (ref "C55") (pin "1") (pinfunction "1_1") (pintype "passive"))
      (node (ref "C59") (pin "1") (pinfunction "1_1") (pintype "passive"))
      (node (ref "U5") (pin "22") (pinfunction "VBB1_22") (pintype "passive"))
      (node (ref "U5") (pin "28") (pinfunction "VBB2_28") (pintype "passive"))
      (node (ref "U8") (pin "22") (pinfunction "VBB1_22") (pintype "passive"))
      (node (ref "U8") (pin "28") (pinfunction "VBB2_28") (pintype "passive"))
    )
    (net (code "21") (name "GND") (class "Default")
      (node (ref "C29") (pin "2") (pinfunction "2_2") (pintype "passive"))
      (node (ref "C52") (pin "2") (pinfunction "2_2") (pintype "passive"))
      (node (ref "C53") (pin "2") (pinfunction "2_2") (pintype "passive"))
      (node (ref "C54") (pin "2") (pinfunction "2_2") (pintype "passive"))
      (node (ref "C55") (pin "2") (pinfunction "2_2") (pintype "passive"))
      (node (ref "C58") (pin "2") (pinfunction "2_2") (pintype "passive"))
      (node (ref "C61") (pin "2") (pinfunction "2_2") (pintype "passive"))
      (node (ref "C63") (pin "2") (pinfunction "2_2") (pintype "passive"))
      (node (ref "NP1") (pin "1") (pinfunction "1_1") (pintype "passive"))
      (node (ref "NP2") (pin "1") (pinfunction "1_1") (pintype "passive"))
      (node (ref "NP3") (pin "1") (pinfunction "1_1") (pintype "passive"))
      (node (ref "NP4") (pin "1") (pinfunction "1_1") (pintype "passive"))
      (node (ref "NP5") (pin "1") (pinfunction "1_1") (pintype "passive"))
      (node (ref "NP6") (pin "1") (pinfunction "1_1") (pintype "passive"))
      (node (ref "NP7") (pin "1") (pinfunction "1_1") (pintype "passive"))
      (node (ref "NP8") (pin "1") (pinfunction "1_1") (pintype "passive"))
      (node (ref "R104") (pin "2") (pinfunction "2_2") (pintype "passive"))
      (node (ref "R28") (pin "2") (pinfunction "2_2") (pintype "passive"))
      (node (ref "R29") (pin "2") (pinfunction "2_2") (pintype "passive"))
      (node (ref "R31") (pin "2") (pinfunction "2_2") (pintype "passive"))
      (node (ref "R32") (pin "2") (pinfunction "2_2") (pintype "passive"))
      (node (ref "R35") (pin "2") (pinfunction "2_2") (pintype "passive"))
      (node (ref "R36") (pin "2") (pinfunction "2_2") (pintype "passive"))
      (node (ref "R37") (pin "2") (pinfunction "2_2") (pintype "passive"))
      (node (ref "R38") (pin "2") (pinfunction "2_2") (pintype "passive"))
      (node (ref "R40") (pin "2") (pinfunction "2_2") (pintype "passive"))
      (node (ref "R41") (pin "2") (pinfunction "2_2") (pintype "passive"))
      (node (ref "R43") (pin "2") (pinfunction "2_2") (pintype "passive"))
      (node (ref "R44") (pin "2") (pinfunction "2_2") (pintype "passive"))
      (node (ref "R48") (pin "2") (pinfunction "2_2") (pintype "passive"))
      (node (ref "R50") (pin "2") (pinfunction "2_2") (pintype "passive"))
      (node (ref "R64") (pin "2") (pinfunction "2_2") (pintype "passive"))
      (node (ref "R69") (pin "2") (pinfunction "2_2") (pintype "passive"))
      (node (ref "R75") (pin "2") (pinfunction "2_2") (pintype "passive"))
      (node (ref "R77") (pin "2") (pinfunction "2_2") (pintype "passive"))
      (node (ref "R91") (pin "2") (pinfunction "2_2") (pintype "passive"))
      (node (ref "U5") (pin "18") (pinfunction "GND_18") (pintype "passive"))
      (node (ref "U5") (pin "29") (pinfunction "PAD_29") (pintype "passive"))
      (node (ref "U5") (pin "3") (pinfunction "GND_3") (pintype "passive"))
      (node (ref "U8") (pin "18") (pinfunction "GND_18") (pintype "passive"))
      (node (ref "U8") (pin "29") (pinfunction "PAD_29") (pintype "passive"))
      (node (ref "U8") (pin "3") (pinfunction "GND_3") (pintype "passive"))
    )
    (net (code "22") (name "Net-(J1-Pad1)") (class "Default")
      (node (ref "J1") (pin "1") (pinfunction "1_1") (pintype "passive"))
      (node (ref "NP1") (pin "2") (pinfunction "2_2") (pintype "passive"))
      (node (ref "R27") (pin "2") (pinfunction "2_2") (pintype "passive"))
      (node (ref "TP8") (pin "1") (pinfunction "1_1") (pintype "passive"))
    )
    (net (code "23") (name "Net-(J1-Pad2)") (class "Default")
      (node (ref "J1") (pin "2") (pinfunction "2_2") (pintype "passive"))
      (node (ref "NP2") (pin "2") (pinfunction "2_2") (pintype "passive"))
      (node (ref "R95") (pin "2") (pinfunction "2_2") (pintype "passive"))
      (node (ref "TP9") (pin "1") (pinfunction "1_1") (pintype "passive"))
    )
    (net (code "24") (name "Net-(J1-Pad3)") (class "Default")
      (node (ref "J1") (pin "3") (pinfunction "3_3") (pintype "passive"))
      (node (ref "NP3") (pin "2") (pinfunction "2_2") (pintype "passive"))
      (node (ref "R96") (pin "2") (pinfunction "2_2") (pintype "passive"))
      (node (ref "TP11") (pin "1") (pinfunction "1_1") (pintype "passive"))
    )
    (net (code "25") (name "Net-(J1-Pad4)") (class "Default")
      (node (ref "J1") (pin "4") (pinfunction "4_4") (pintype "passive"))
      (node (ref "NP4") (pin "2") (pinfunction "2_2") (pintype "passive"))
      (node (ref "R97") (pin "2") (pinfunction "2_2") (pintype "passive"))
      (node (ref "TP10") (pin "1") (pinfunction "1_1") (pintype "passive"))
    )
    (net (code "26") (name "Net-(J6-Pad1)") (class "Default")
      (node (ref "J6") (pin "1") (pinfunction "1_1") (pintype "passive"))
      (node (ref "NP5") (pin "2") (pinfunction "2_2") (pintype "passive"))
      (node (ref "R98") (pin "2") (pinfunction "2_2") (pintype "passive"))
      (node (ref "TP12") (pin "1") (pinfunction "1_1") (pintype "passive"))
    )
    (net (code "27") (name "Net-(J6-Pad2)") (class "Default")
      (node (ref "J6") (pin "2") (pinfunction "2_2") (pintype "passive"))
      (node (ref "NP6") (pin "2") (pinfunction "2_2") (pintype "passive"))
      (node (ref "R99") (pin "2") (pinfunction "2_2") (pintype "passive"))
      (node (ref "TP13") (pin "1") (pinfunction "1_1") (pintype "passive"))
    )
    (net (code "28") (name "Net-(J6-Pad3)") (class "Default")
      (node (ref "J6") (pin "3") (pinfunction "3_3") (pintype "passive"))
      (node (ref "NP7") (pin "2") (pinfunction "2_2") (pintype "passive"))
      (node (ref "R100") (pin "2") (pinfunction "2_2") (pintype "passive"))
      (node (ref "TP14") (pin "1") (pinfunction "1_1") (pintype "passive"))
    )
    (net (code "29") (name "Net-(J6-Pad4)") (class "Default")
      (node (ref "J6") (pin "4") (pinfunction "4_4") (pintype "passive"))
      (node (ref "NP8") (pin "2") (pinfunction "2_2") (pintype "passive"))
      (node (ref "R101") (pin "2") (pinfunction "2_2") (pintype "passive"))
      (node (ref "TP15") (pin "1") (pinfunction "1_1") (pintype "passive"))
    )
    (net (code "30") (name "Net-(U5-CP1)") (class "Default")
      (node (ref "C60") (pin "2") (pinfunction "2_2") (pintype "passive"))
      (node (ref "U5") (pin "4") (pinfunction "CP1_4") (pintype "passive"))
    )
    (net (code "31") (name "Net-(U5-CP2)") (class "Default")
      (node (ref "C60") (pin "1") (pinfunction "1_1") (pintype "passive"))
      (node (ref "U5") (pin "5") (pinfunction "CP2_5") (pintype "passive"))
    )
    (net (code "32") (name "Net-(U5-MS1)") (class "Default")
      (node (ref "R39") (pin "2") (pinfunction "2_2") (pintype "passive"))
      (node (ref "R41") (pin "1") (pinfunction "1_1") (pintype "passive"))
      (node (ref "TP39") (pin "1") (pinfunction "1_1") (pintype "passive"))
      (node (ref "U5") (pin "9") (pinfunction "MS1_9") (pintype "passive"))
    )
    (net (code "33") (name "Net-(U5-MS2)") (class "Default")
      (node (ref "R42") (pin "2") (pinfunction "2_2") (pintype "passive"))
      (node (ref "R43") (pin "1") (pinfunction "1_1") (pintype "passive"))
      (node (ref "TP40") (pin "1") (pinfunction "1_1") (pintype "passive"))
      (node (ref "U5") (pin "10") (pinfunction "MS2_10") (pintype "passive"))
    )
    (net (code "34") (name "Net-(U5-MS3)") (class "Default")
      (node (ref "R34") (pin "2") (pinfunction "2_2") (pintype "passive"))
      (node (ref "R38") (pin "1") (pinfunction "1_1") (pintype "passive"))
      (node (ref "TP41") (pin "1") (pinfunction "1_1") (pintype "passive"))
      (node (ref "U5") (pin "11") (pinfunction "MS3_11") (pintype "passive"))
    )
    (net (code "35") (name "Net-(U5-REF)") (class "Default")
      (node (ref "R48") (pin "1") (pinfunction "1_1") (pintype "passive"))
      (node (ref "R49") (pin "2") (pinfunction "2_2") (pintype "passive"))
      (node (ref "U5") (pin "17") (pinfunction "REF_17") (pintype "passive"))
    )
    (net (code "36") (name "Net-(U5-ROSC)") (class "Default")
      (node (ref "R35") (pin "1") (pinfunction "1_1") (pintype "passive"))
      (node (ref "U5") (pin "13") (pinfunction "ROSC_13") (pintype "passive"))
    )
    (net (code "37") (name "Net-(U5-SENSE1)") (class "Default")
      (node (ref "R31") (pin "1") (pinfunction "1_1") (pintype "passive"))
      (node (ref "U5") (pin "23") (pinfunction "SENSE1_23") (pintype "passive"))
    )
    (net (code "38") (name "Net-(U5-SENSE2)") (class "Default")
      (node (ref "R28") (pin "1") (pinfunction "1_1") (pintype "passive"))
      (node (ref "U5") (pin "27") (pinfunction "SENSE2_27") (pintype "passive"))
    )
    (net (code "39") (name "Net-(U5-VCP)") (class "Default")
      (node (ref "C59") (pin "2") (pinfunction "2_2") (pintype "passive"))
      (node (ref "U5") (pin "6") (pinfunction "VCP_6") (pintype "passive"))
    )
    (net (code "40") (name "Net-(U5-VREG)") (class "Default")
      (node (ref "C63") (pin "1") (pinfunction "1_1") (pintype "passive"))
      (node (ref "U5") (pin "8") (pinfunction "VREG_8") (pintype "passive"))
    )
    (net (code "41") (name "Net-(U8-CP1)") (class "Default")
      (node (ref "C28") (pin "2") (pinfunction "2_2") (pintype "passive"))
      (node (ref "U8") (pin "4") (pinfunction "CP1_4") (pintype "passive"))
    )
    (net (code "42") (name "Net-(U8-CP2)") (class "Default")
      (node (ref "C28") (pin "1") (pinfunction "1_1") (pintype "passive"))
      (node (ref "U8") (pin "5") (pinfunction "CP2_5") (pintype "passive"))
    )
    (net (code "43") (name "Net-(U8-MS1)") (class "Default")
      (node (ref "R74") (pin "2") (pinfunction "2_2") (pintype "passive"))
      (node (ref "R75") (pin "1") (pinfunction "1_1") (pintype "passive"))
      (node (ref "TP44") (pin "1") (pinfunction "1_1") (pintype "passive"))
      (node (ref "U8") (pin "9") (pinfunction "MS1_9") (pintype "passive"))
    )
    (net (code "44") (name "Net-(U8-MS2)") (class "Default")
      (node (ref "R76") (pin "2") (pinfunction "2_2") (pintype "passive"))
      (node (ref "R77") (pin "1") (pinfunction "1_1") (pintype "passive"))
      (node (ref "TP45") (pin "1") (pinfunction "1_1") (pintype "passive"))
      (node (ref "U8") (pin "10") (pinfunction "MS2_10") (pintype "passive"))
    )
    (net (code "45") (name "Net-(U8-MS3)") (class "Default")
      (node (ref "R68") (pin "2") (pinfunction "2_2") (pintype "passive"))
      (node (ref "R69") (pin "1") (pinfunction "1_1") (pintype "passive"))
      (node (ref "TP46") (pin "1") (pinfunction "1_1") (pintype "passive"))
      (node (ref "U8") (pin "11") (pinfunction "MS3_11") (pintype "passive"))
    )
    (net (code "46") (name "Net-(U8-REF)") (class "Default")
      (node (ref "R50") (pin "1") (pinfunction "1_1") (pintype "passive"))
      (node (ref "R56") (pin "2") (pinfunction "2_2") (pintype "passive"))
      (node (ref "U8") (pin "17") (pinfunction "REF_17") (pintype "passive"))
    )
    (net (code "47") (name "Net-(U8-ROSC)") (class "Default")
      (node (ref "R40") (pin "1") (pinfunction "1_1") (pintype "passive"))
      (node (ref "U8") (pin "13") (pinfunction "ROSC_13") (pintype "passive"))
    )
    (net (code "48") (name "Net-(U8-SENSE1)") (class "Default")
      (node (ref "R37") (pin "1") (pinfunction "1_1") (pintype "passive"))
      (node (ref "U8") (pin "23") (pinfunction "SENSE1_23") (pintype "passive"))
    )
    (net (code "49") (name "Net-(U8-SENSE2)") (class "Default")
      (node (ref "R36") (pin "1") (pinfunction "1_1") (pintype "passive"))
      (node (ref "U8") (pin "27") (pinfunction "SENSE2_27") (pintype "passive"))
    )
    (net (code "50") (name "Net-(U8-VCP)") (class "Default")
      (node (ref "C27") (pin "2") (pinfunction "2_2") (pintype "passive"))
      (node (ref "U8") (pin "6") (pinfunction "VCP_6") (pintype "passive"))
    )
    (net (code "51") (name "Net-(U8-VREG)") (class "Default")
      (node (ref "C29") (pin "1") (pinfunction "1_1") (pintype "passive"))
      (node (ref "U8") (pin "8") (pinfunction "VREG_8") (pintype "passive"))
    )
    (net (code "52") (name "unconnected-(U5-NC-Pad7)") (class "Default")
      (node (ref "U5") (pin "7") (pinfunction "NC_7") (pintype "passive+no_connect"))
    )
    (net (code "53") (name "unconnected-(U5-NC-Pad20)") (class "Default")
      (node (ref "U5") (pin "20") (pinfunction "NC_20") (pintype "passive+no_connect"))
    )
    (net (code "54") (name "unconnected-(U5-NC-Pad25)") (class "Default")
      (node (ref "U5") (pin "25") (pinfunction "NC_25") (pintype "passive+no_connect"))
    )
    (net (code "55") (name "unconnected-(U8-NC-Pad7)") (class "Default")
      (node (ref "U8") (pin "7") (pinfunction "NC_7") (pintype "passive+no_connect"))
    )
    (net (code "56") (name "unconnected-(U8-NC-Pad20)") (class "Default")
      (node (ref "U8") (pin "20") (pinfunction "NC_20") (pintype "passive+no_connect"))
    )
    (net (code "57") (name "unconnected-(U8-NC-Pad25)") (class "Default")
      (node (ref "U8") (pin "25") (pinfunction "NC_25") (pintype "passive+no_connect"))
    )
  )
)
